# mainboard.net
KiCad netlist of a schematic drawn in EAGLE
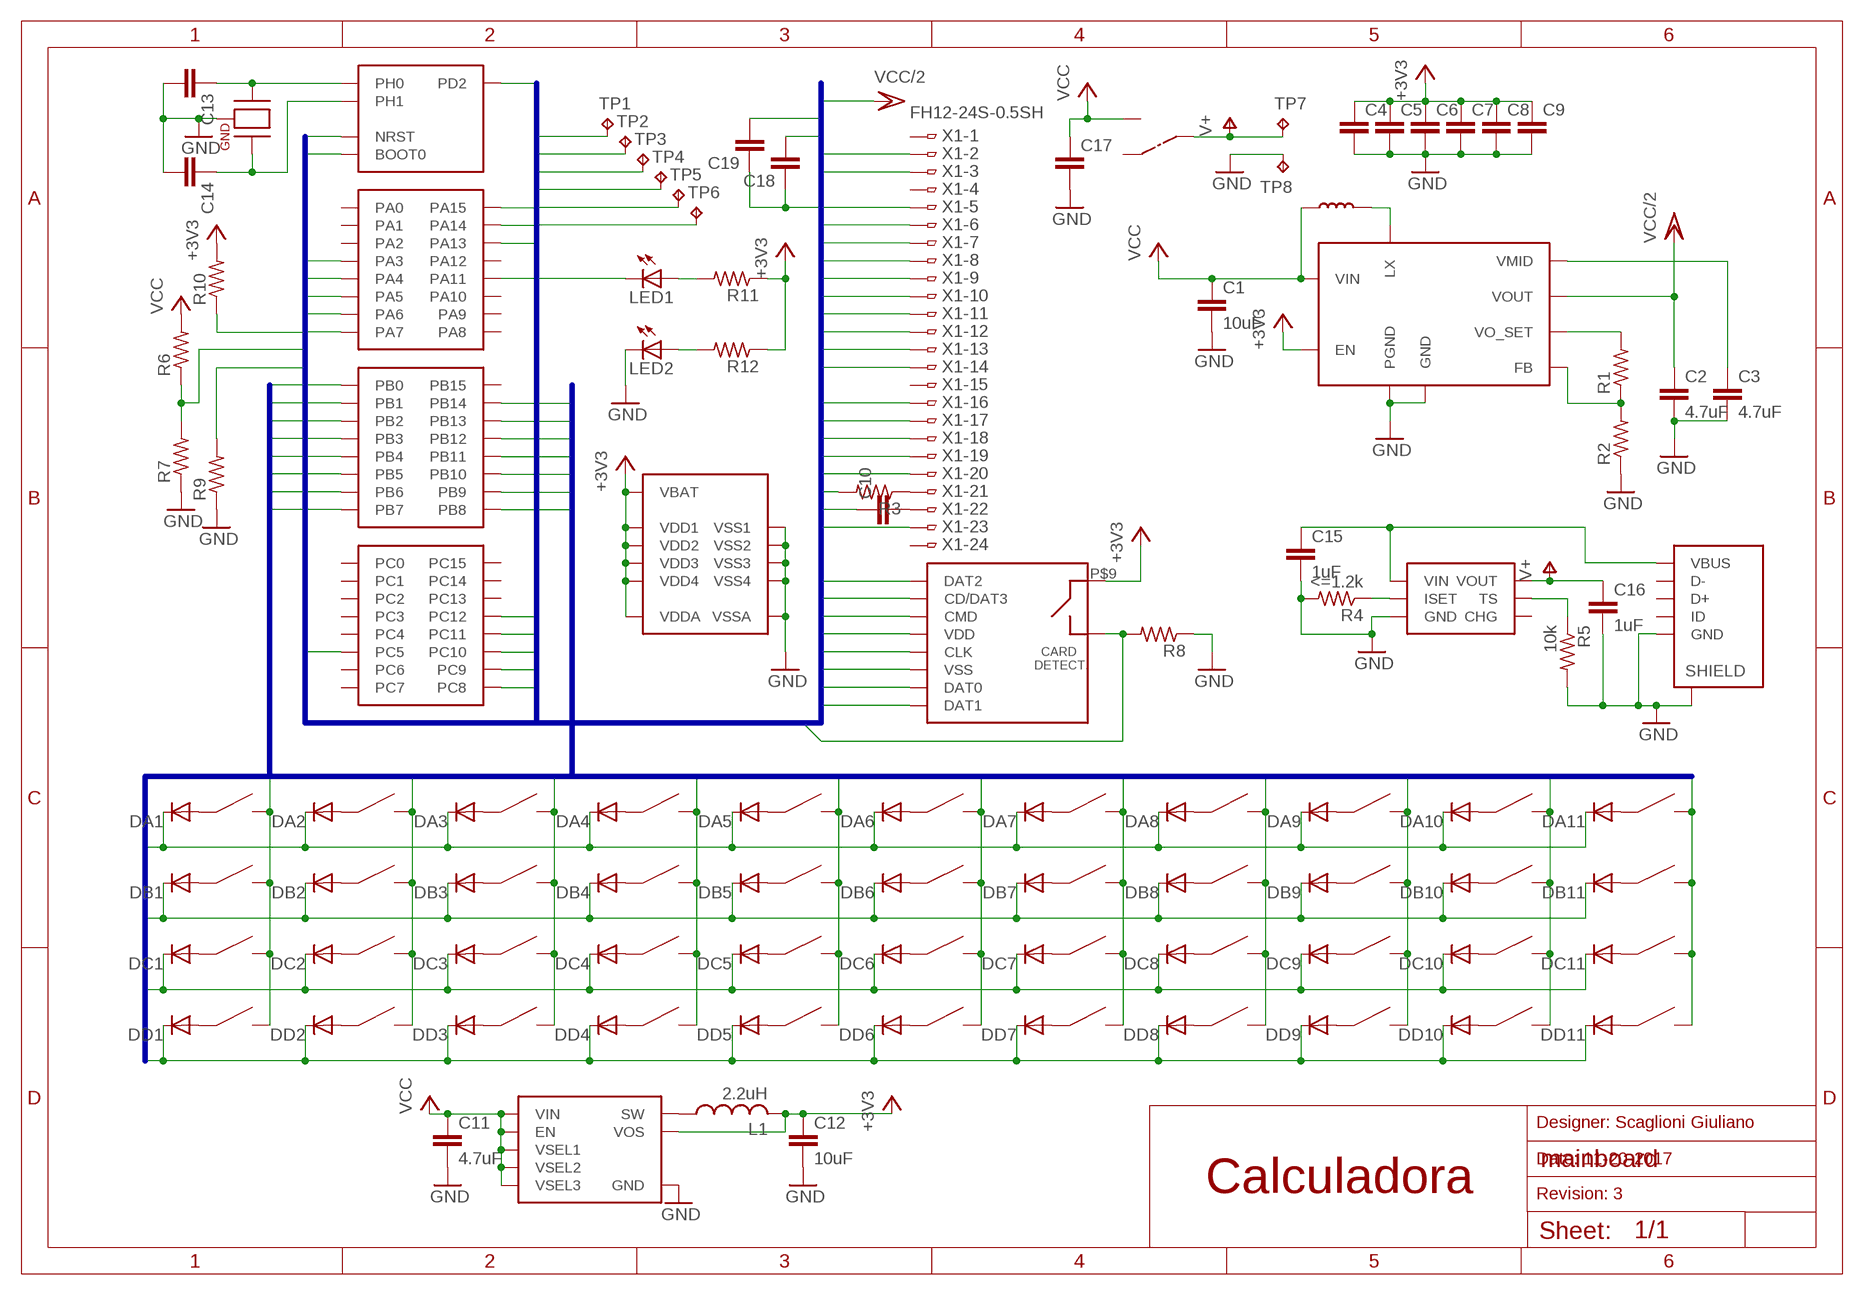
[diagram p0: schematic, sheet 1]

(export (version "E")
  (design (tool "Eeschema 10.0.6"))
  (components
    (comp (ref "BTA1")
      (value "WURTH_SWITCH")
      (footprint "eagle-import:WURTH_SWITCH_SMD")
      (libsource (lib "eagle-import") (part "WURTH_SWITCH"))
    )
    (comp (ref "BTA2")
      (value "WURTH_SWITCH")
      (footprint "eagle-import:WURTH_SWITCH_SMD")
      (libsource (lib "eagle-import") (part "WURTH_SWITCH"))
    )
    (comp (ref "BTA3")
      (value "WURTH_SWITCH")
      (footprint "eagle-import:WURTH_SWITCH_SMD")
      (libsource (lib "eagle-import") (part "WURTH_SWITCH"))
    )
    (comp (ref "BTA4")
      (value "WURTH_SWITCH")
      (footprint "eagle-import:WURTH_SWITCH_SMD")
      (libsource (lib "eagle-import") (part "WURTH_SWITCH"))
    )
    (comp (ref "BTA5")
      (value "WURTH_SWITCH")
      (footprint "eagle-import:WURTH_SWITCH_SMD")
      (libsource (lib "eagle-import") (part "WURTH_SWITCH"))
    )
    (comp (ref "BTA6")
      (value "WURTH_SWITCH")
      (footprint "eagle-import:WURTH_SWITCH_SMD")
      (libsource (lib "eagle-import") (part "WURTH_SWITCH"))
    )
    (comp (ref "BTA7")
      (value "WURTH_SWITCH")
      (footprint "eagle-import:WURTH_SWITCH_SMD")
      (libsource (lib "eagle-import") (part "WURTH_SWITCH"))
    )
    (comp (ref "BTA8")
      (value "WURTH_SWITCH")
      (footprint "eagle-import:WURTH_SWITCH_SMD")
      (libsource (lib "eagle-import") (part "WURTH_SWITCH"))
    )
    (comp (ref "BTA9")
      (value "WURTH_SWITCH")
      (footprint "eagle-import:WURTH_SWITCH_SMD")
      (libsource (lib "eagle-import") (part "WURTH_SWITCH"))
    )
    (comp (ref "BTA10")
      (value "WURTH_SWITCH")
      (footprint "eagle-import:WURTH_SWITCH_SMD")
      (libsource (lib "eagle-import") (part "WURTH_SWITCH"))
    )
    (comp (ref "BTA11")
      (value "WURTH_SWITCH")
      (footprint "eagle-import:WURTH_SWITCH_SMD")
      (libsource (lib "eagle-import") (part "WURTH_SWITCH"))
    )
    (comp (ref "BTB1")
      (value "WURTH_SWITCH")
      (footprint "eagle-import:WURTH_SWITCH_SMD")
      (libsource (lib "eagle-import") (part "WURTH_SWITCH"))
    )
    (comp (ref "BTB2")
      (value "WURTH_SWITCH")
      (footprint "eagle-import:WURTH_SWITCH_SMD")
      (libsource (lib "eagle-import") (part "WURTH_SWITCH"))
    )
    (comp (ref "BTB3")
      (value "WURTH_SWITCH")
      (footprint "eagle-import:WURTH_SWITCH_SMD")
      (libsource (lib "eagle-import") (part "WURTH_SWITCH"))
    )
    (comp (ref "BTB4")
      (value "WURTH_SWITCH")
      (footprint "eagle-import:WURTH_SWITCH_SMD")
      (libsource (lib "eagle-import") (part "WURTH_SWITCH"))
    )
    (comp (ref "BTB5")
      (value "WURTH_SWITCH")
      (footprint "eagle-import:WURTH_SWITCH_SMD")
      (libsource (lib "eagle-import") (part "WURTH_SWITCH"))
    )
    (comp (ref "BTB6")
      (value "WURTH_SWITCH")
      (footprint "eagle-import:WURTH_SWITCH_SMD")
      (libsource (lib "eagle-import") (part "WURTH_SWITCH"))
    )
    (comp (ref "BTB7")
      (value "WURTH_SWITCH")
      (footprint "eagle-import:WURTH_SWITCH_SMD")
      (libsource (lib "eagle-import") (part "WURTH_SWITCH"))
    )
    (comp (ref "BTB8")
      (value "WURTH_SWITCH")
      (footprint "eagle-import:WURTH_SWITCH_SMD")
      (libsource (lib "eagle-import") (part "WURTH_SWITCH"))
    )
    (comp (ref "BTB9")
      (value "WURTH_SWITCH")
      (footprint "eagle-import:WURTH_SWITCH_SMD")
      (libsource (lib "eagle-import") (part "WURTH_SWITCH"))
    )
    (comp (ref "BTB10")
      (value "WURTH_SWITCH")
      (footprint "eagle-import:WURTH_SWITCH_SMD")
      (libsource (lib "eagle-import") (part "WURTH_SWITCH"))
    )
    (comp (ref "BTB11")
      (value "WURTH_SWITCH")
      (footprint "eagle-import:WURTH_SWITCH_SMD")
      (libsource (lib "eagle-import") (part "WURTH_SWITCH"))
    )
    (comp (ref "BTC1")
      (value "WURTH_SWITCH")
      (footprint "eagle-import:WURTH_SWITCH_SMD")
      (libsource (lib "eagle-import") (part "WURTH_SWITCH"))
    )
    (comp (ref "BTC2")
      (value "WURTH_SWITCH")
      (footprint "eagle-import:WURTH_SWITCH_SMD")
      (libsource (lib "eagle-import") (part "WURTH_SWITCH"))
    )
    (comp (ref "BTC3")
      (value "WURTH_SWITCH")
      (footprint "eagle-import:WURTH_SWITCH_SMD")
      (libsource (lib "eagle-import") (part "WURTH_SWITCH"))
    )
    (comp (ref "BTC4")
      (value "WURTH_SWITCH")
      (footprint "eagle-import:WURTH_SWITCH_SMD")
      (libsource (lib "eagle-import") (part "WURTH_SWITCH"))
    )
    (comp (ref "BTC5")
      (value "WURTH_SWITCH")
      (footprint "eagle-import:WURTH_SWITCH_SMD")
      (libsource (lib "eagle-import") (part "WURTH_SWITCH"))
    )
    (comp (ref "BTC6")
      (value "WURTH_SWITCH")
      (footprint "eagle-import:WURTH_SWITCH_SMD")
      (libsource (lib "eagle-import") (part "WURTH_SWITCH"))
    )
    (comp (ref "BTC7")
      (value "WURTH_SWITCH")
      (footprint "eagle-import:WURTH_SWITCH_SMD")
      (libsource (lib "eagle-import") (part "WURTH_SWITCH"))
    )
    (comp (ref "BTC8")
      (value "WURTH_SWITCH")
      (footprint "eagle-import:WURTH_SWITCH_SMD")
      (libsource (lib "eagle-import") (part "WURTH_SWITCH"))
    )
    (comp (ref "BTC9")
      (value "WURTH_SWITCH")
      (footprint "eagle-import:WURTH_SWITCH_SMD")
      (libsource (lib "eagle-import") (part "WURTH_SWITCH"))
    )
    (comp (ref "BTC10")
      (value "WURTH_SWITCH")
      (footprint "eagle-import:WURTH_SWITCH_SMD")
      (libsource (lib "eagle-import") (part "WURTH_SWITCH"))
    )
    (comp (ref "BTC11")
      (value "WURTH_SWITCH")
      (footprint "eagle-import:WURTH_SWITCH_SMD")
      (libsource (lib "eagle-import") (part "WURTH_SWITCH"))
    )
    (comp (ref "BTD1")
      (value "WURTH_SWITCH")
      (footprint "eagle-import:WURTH_SWITCH_SMD")
      (libsource (lib "eagle-import") (part "WURTH_SWITCH"))
    )
    (comp (ref "BTD2")
      (value "WURTH_SWITCH")
      (footprint "eagle-import:WURTH_SWITCH_SMD")
      (libsource (lib "eagle-import") (part "WURTH_SWITCH"))
    )
    (comp (ref "BTD3")
      (value "WURTH_SWITCH")
      (footprint "eagle-import:WURTH_SWITCH_SMD")
      (libsource (lib "eagle-import") (part "WURTH_SWITCH"))
    )
    (comp (ref "BTD4")
      (value "WURTH_SWITCH")
      (footprint "eagle-import:WURTH_SWITCH_SMD")
      (libsource (lib "eagle-import") (part "WURTH_SWITCH"))
    )
    (comp (ref "BTD5")
      (value "WURTH_SWITCH")
      (footprint "eagle-import:WURTH_SWITCH_SMD")
      (libsource (lib "eagle-import") (part "WURTH_SWITCH"))
    )
    (comp (ref "BTD6")
      (value "WURTH_SWITCH")
      (footprint "eagle-import:WURTH_SWITCH_SMD")
      (libsource (lib "eagle-import") (part "WURTH_SWITCH"))
    )
    (comp (ref "BTD7")
      (value "WURTH_SWITCH")
      (footprint "eagle-import:WURTH_SWITCH_SMD")
      (libsource (lib "eagle-import") (part "WURTH_SWITCH"))
    )
    (comp (ref "BTD8")
      (value "WURTH_SWITCH")
      (footprint "eagle-import:WURTH_SWITCH_SMD")
      (libsource (lib "eagle-import") (part "WURTH_SWITCH"))
    )
    (comp (ref "BTD9")
      (value "WURTH_SWITCH")
      (footprint "eagle-import:WURTH_SWITCH_SMD")
      (libsource (lib "eagle-import") (part "WURTH_SWITCH"))
    )
    (comp (ref "BTD10")
      (value "WURTH_SWITCH")
      (footprint "eagle-import:WURTH_SWITCH_SMD")
      (libsource (lib "eagle-import") (part "WURTH_SWITCH"))
    )
    (comp (ref "BTD11")
      (value "WURTH_SWITCH")
      (footprint "eagle-import:WURTH_SWITCH_SMD")
      (libsource (lib "eagle-import") (part "WURTH_SWITCH"))
    )
    (comp (ref "C1")
      (value "10uF")
      (footprint "eagle-import:C0805")
      (libsource (lib "eagle-import") (part "resistor_348_C-EUC0805"))
    )
    (comp (ref "C2")
      (value "4.7uF")
      (footprint "eagle-import:C0805")
      (libsource (lib "eagle-import") (part "resistor_348_C-EUC0805"))
    )
    (comp (ref "C3")
      (value "4.7uF")
      (footprint "eagle-import:C0805")
      (libsource (lib "eagle-import") (part "resistor_348_C-EUC0805"))
    )
    (comp (ref "C4")
      (value "C-EUC0603")
      (footprint "eagle-import:C0603")
      (libsource (lib "eagle-import") (part "C-EUC0603"))
    )
    (comp (ref "C5")
      (value "C-EUC0603")
      (footprint "eagle-import:C0603")
      (libsource (lib "eagle-import") (part "C-EUC0603"))
    )
    (comp (ref "C6")
      (value "C-EUC0603")
      (footprint "eagle-import:C0603")
      (libsource (lib "eagle-import") (part "C-EUC0603"))
    )
    (comp (ref "C7")
      (value "C-EUC0603")
      (footprint "eagle-import:C0603")
      (libsource (lib "eagle-import") (part "C-EUC0603"))
    )
    (comp (ref "C8")
      (value "C-EUC0603")
      (footprint "eagle-import:C0603")
      (libsource (lib "eagle-import") (part "C-EUC0603"))
    )
    (comp (ref "C9")
      (value "C-EUC0603")
      (footprint "eagle-import:C0603")
      (libsource (lib "eagle-import") (part "C-EUC0603"))
    )
    (comp (ref "C10")
      (value "C-EUC0603")
      (footprint "eagle-import:C0603")
      (libsource (lib "eagle-import") (part "C-EUC0603"))
    )
    (comp (ref "C11")
      (value "4.7uF")
      (footprint "eagle-import:C0603")
      (libsource (lib "eagle-import") (part "C-EUC0603"))
    )
    (comp (ref "C12")
      (value "10uF")
      (footprint "eagle-import:C0603")
      (libsource (lib "eagle-import") (part "C-EUC0603"))
    )
    (comp (ref "C13")
      (value "CC0603")
      (footprint "eagle-import:C0603")
      (libsource (lib "eagle-import") (part "CC0603"))
    )
    (comp (ref "C14")
      (value "CC0603")
      (footprint "eagle-import:C0603")
      (libsource (lib "eagle-import") (part "CC0603"))
    )
    (comp (ref "C15")
      (value "1uF")
      (footprint "eagle-import:C0603")
      (libsource (lib "eagle-import") (part "C-EUC0603"))
    )
    (comp (ref "C16")
      (value "1uF")
      (footprint "eagle-import:C0603")
      (libsource (lib "eagle-import") (part "C-EUC0603"))
    )
    (comp (ref "C17")
      (value "CC1206")
      (footprint "eagle-import:C1206")
      (libsource (lib "eagle-import") (part "CC1206"))
    )
    (comp (ref "C18")
      (value "C-EUC0603")
      (footprint "eagle-import:C0603")
      (libsource (lib "eagle-import") (part "C-EUC0603"))
    )
    (comp (ref "C19")
      (value "C-EUC0603")
      (footprint "eagle-import:C0603")
      (libsource (lib "eagle-import") (part "C-EUC0603"))
    )
    (comp (ref "DA1")
      (value "DIODE-SOD523")
      (footprint "eagle-import:SOD523")
      (libsource (lib "eagle-import") (part "DIODE-SOD523"))
    )
    (comp (ref "DA2")
      (value "DIODE-SOD523")
      (footprint "eagle-import:SOD523")
      (libsource (lib "eagle-import") (part "DIODE-SOD523"))
    )
    (comp (ref "DA3")
      (value "DIODE-SOD523")
      (footprint "eagle-import:SOD523")
      (libsource (lib "eagle-import") (part "DIODE-SOD523"))
    )
    (comp (ref "DA4")
      (value "DIODE-SOD523")
      (footprint "eagle-import:SOD523")
      (libsource (lib "eagle-import") (part "DIODE-SOD523"))
    )
    (comp (ref "DA5")
      (value "DIODE-SOD523")
      (footprint "eagle-import:SOD523")
      (libsource (lib "eagle-import") (part "DIODE-SOD523"))
    )
    (comp (ref "DA6")
      (value "DIODE-SOD523")
      (footprint "eagle-import:SOD523")
      (libsource (lib "eagle-import") (part "DIODE-SOD523"))
    )
    (comp (ref "DA7")
      (value "DIODE-SOD523")
      (footprint "eagle-import:SOD523")
      (libsource (lib "eagle-import") (part "DIODE-SOD523"))
    )
    (comp (ref "DA8")
      (value "DIODE-SOD523")
      (footprint "eagle-import:SOD523")
      (libsource (lib "eagle-import") (part "DIODE-SOD523"))
    )
    (comp (ref "DA9")
      (value "DIODE-SOD523")
      (footprint "eagle-import:SOD523")
      (libsource (lib "eagle-import") (part "DIODE-SOD523"))
    )
    (comp (ref "DA10")
      (value "DIODE-SOD523")
      (footprint "eagle-import:SOD523")
      (libsource (lib "eagle-import") (part "DIODE-SOD523"))
    )
    (comp (ref "DA11")
      (value "DIODE-SOD523")
      (footprint "eagle-import:SOD523")
      (libsource (lib "eagle-import") (part "DIODE-SOD523"))
    )
    (comp (ref "DB1")
      (value "DIODE-SOD523")
      (footprint "eagle-import:SOD523")
      (libsource (lib "eagle-import") (part "DIODE-SOD523"))
    )
    (comp (ref "DB2")
      (value "DIODE-SOD523")
      (footprint "eagle-import:SOD523")
      (libsource (lib "eagle-import") (part "DIODE-SOD523"))
    )
    (comp (ref "DB3")
      (value "DIODE-SOD523")
      (footprint "eagle-import:SOD523")
      (libsource (lib "eagle-import") (part "DIODE-SOD523"))
    )
    (comp (ref "DB4")
      (value "DIODE-SOD523")
      (footprint "eagle-import:SOD523")
      (libsource (lib "eagle-import") (part "DIODE-SOD523"))
    )
    (comp (ref "DB5")
      (value "DIODE-SOD523")
      (footprint "eagle-import:SOD523")
      (libsource (lib "eagle-import") (part "DIODE-SOD523"))
    )
    (comp (ref "DB6")
      (value "DIODE-SOD523")
      (footprint "eagle-import:SOD523")
      (libsource (lib "eagle-import") (part "DIODE-SOD523"))
    )
    (comp (ref "DB7")
      (value "DIODE-SOD523")
      (footprint "eagle-import:SOD523")
      (libsource (lib "eagle-import") (part "DIODE-SOD523"))
    )
    (comp (ref "DB8")
      (value "DIODE-SOD523")
      (footprint "eagle-import:SOD523")
      (libsource (lib "eagle-import") (part "DIODE-SOD523"))
    )
    (comp (ref "DB9")
      (value "DIODE-SOD523")
      (footprint "eagle-import:SOD523")
      (libsource (lib "eagle-import") (part "DIODE-SOD523"))
    )
    (comp (ref "DB10")
      (value "DIODE-SOD523")
      (footprint "eagle-import:SOD523")
      (libsource (lib "eagle-import") (part "DIODE-SOD523"))
    )
    (comp (ref "DB11")
      (value "DIODE-SOD523")
      (footprint "eagle-import:SOD523")
      (libsource (lib "eagle-import") (part "DIODE-SOD523"))
    )
    (comp (ref "DC1")
      (value "DIODE-SOD523")
      (footprint "eagle-import:SOD523")
      (libsource (lib "eagle-import") (part "DIODE-SOD523"))
    )
    (comp (ref "DC2")
      (value "DIODE-SOD523")
      (footprint "eagle-import:SOD523")
      (libsource (lib "eagle-import") (part "DIODE-SOD523"))
    )
    (comp (ref "DC3")
      (value "DIODE-SOD523")
      (footprint "eagle-import:SOD523")
      (libsource (lib "eagle-import") (part "DIODE-SOD523"))
    )
    (comp (ref "DC4")
      (value "DIODE-SOD523")
      (footprint "eagle-import:SOD523")
      (libsource (lib "eagle-import") (part "DIODE-SOD523"))
    )
    (comp (ref "DC5")
      (value "DIODE-SOD523")
      (footprint "eagle-import:SOD523")
      (libsource (lib "eagle-import") (part "DIODE-SOD523"))
    )
    (comp (ref "DC6")
      (value "DIODE-SOD523")
      (footprint "eagle-import:SOD523")
      (libsource (lib "eagle-import") (part "DIODE-SOD523"))
    )
    (comp (ref "DC7")
      (value "DIODE-SOD523")
      (footprint "eagle-import:SOD523")
      (libsource (lib "eagle-import") (part "DIODE-SOD523"))
    )
    (comp (ref "DC8")
      (value "DIODE-SOD523")
      (footprint "eagle-import:SOD523")
      (libsource (lib "eagle-import") (part "DIODE-SOD523"))
    )
    (comp (ref "DC9")
      (value "DIODE-SOD523")
      (footprint "eagle-import:SOD523")
      (libsource (lib "eagle-import") (part "DIODE-SOD523"))
    )
    (comp (ref "DC10")
      (value "DIODE-SOD523")
      (footprint "eagle-import:SOD523")
      (libsource (lib "eagle-import") (part "DIODE-SOD523"))
    )
    (comp (ref "DC11")
      (value "DIODE-SOD523")
      (footprint "eagle-import:SOD523")
      (libsource (lib "eagle-import") (part "DIODE-SOD523"))
    )
    (comp (ref "DD1")
      (value "DIODE-SOD523")
      (footprint "eagle-import:SOD523")
      (libsource (lib "eagle-import") (part "DIODE-SOD523"))
    )
    (comp (ref "DD2")
      (value "DIODE-SOD523")
      (footprint "eagle-import:SOD523")
      (libsource (lib "eagle-import") (part "DIODE-SOD523"))
    )
    (comp (ref "DD3")
      (value "DIODE-SOD523")
      (footprint "eagle-import:SOD523")
      (libsource (lib "eagle-import") (part "DIODE-SOD523"))
    )
    (comp (ref "DD4")
      (value "DIODE-SOD523")
      (footprint "eagle-import:SOD523")
      (libsource (lib "eagle-import") (part "DIODE-SOD523"))
    )
    (comp (ref "DD5")
      (value "DIODE-SOD523")
      (footprint "eagle-import:SOD523")
      (libsource (lib "eagle-import") (part "DIODE-SOD523"))
    )
    (comp (ref "DD6")
      (value "DIODE-SOD523")
      (footprint "eagle-import:SOD523")
      (libsource (lib "eagle-import") (part "DIODE-SOD523"))
    )
    (comp (ref "DD7")
      (value "DIODE-SOD523")
      (footprint "eagle-import:SOD523")
      (libsource (lib "eagle-import") (part "DIODE-SOD523"))
    )
    (comp (ref "DD8")
      (value "DIODE-SOD523")
      (footprint "eagle-import:SOD523")
      (libsource (lib "eagle-import") (part "DIODE-SOD523"))
    )
    (comp (ref "DD9")
      (value "DIODE-SOD523")
      (footprint "eagle-import:SOD523")
      (libsource (lib "eagle-import") (part "DIODE-SOD523"))
    )
    (comp (ref "DD10")
      (value "DIODE-SOD523")
      (footprint "eagle-import:SOD523")
      (libsource (lib "eagle-import") (part "DIODE-SOD523"))
    )
    (comp (ref "DD11")
      (value "DIODE-SOD523")
      (footprint "eagle-import:SOD523")
      (libsource (lib "eagle-import") (part "DIODE-SOD523"))
    )
    (comp (ref "L1")
      (value "2.2uH")
      (footprint "eagle-import:L2012C")
      (libsource (lib "eagle-import") (part "L-USL2012C"))
    )
    (comp (ref "LED1")
      (value "LED_ESML0603")
      (footprint "eagle-import:LED_SML0603")
      (libsource (lib "eagle-import") (part "LED_ESML0603"))
    )
    (comp (ref "LED2")
      (value "LED_ESML0603")
      (footprint "eagle-import:LED_SML0603")
      (libsource (lib "eagle-import") (part "LED_ESML0603"))
    )
    (comp (ref "R1")
      (value "R-US_R0402")
      (footprint "eagle-import:R0402")
      (libsource (lib "eagle-import") (part "R-US_R0402"))
    )
    (comp (ref "R2")
      (value "R-US_R0402")
      (footprint "eagle-import:R0402")
      (libsource (lib "eagle-import") (part "R-US_R0402"))
    )
    (comp (ref "R3")
      (value "R-US_R0402")
      (footprint "eagle-import:R0402")
      (libsource (lib "eagle-import") (part "R-US_R0402"))
    )
    (comp (ref "R4")
      (value "<=1.2k")
      (footprint "eagle-import:R0402")
      (libsource (lib "eagle-import") (part "R-US_R0402"))
    )
    (comp (ref "R5")
      (value "10k")
      (footprint "eagle-import:R0402")
      (libsource (lib "eagle-import") (part "R-US_R0402"))
    )
    (comp (ref "R6")
      (value "R-US_R0402")
      (footprint "eagle-import:R0402")
      (libsource (lib "eagle-import") (part "R-US_R0402"))
    )
    (comp (ref "R7")
      (value "R-US_R0402")
      (footprint "eagle-import:R0402")
      (libsource (lib "eagle-import") (part "R-US_R0402"))
    )
    (comp (ref "R8")
      (value "R-US_R0402")
      (footprint "eagle-import:R0402")
      (libsource (lib "eagle-import") (part "R-US_R0402"))
    )
    (comp (ref "R9")
      (value "R-US_R0402")
      (footprint "eagle-import:R0402")
      (libsource (lib "eagle-import") (part "R-US_R0402"))
    )
    (comp (ref "R10")
      (value "R-US_R0402")
      (footprint "eagle-import:R0402")
      (libsource (lib "eagle-import") (part "R-US_R0402"))
    )
    (comp (ref "R11")
      (value "R-US_R0402")
      (footprint "eagle-import:R0402")
      (libsource (lib "eagle-import") (part "R-US_R0402"))
    )
    (comp (ref "R12")
      (value "R-US_R0402")
      (footprint "eagle-import:R0402")
      (libsource (lib "eagle-import") (part "R-US_R0402"))
    )
    (comp (ref "TP1")
      (value "TPTP20SQ")
      (footprint "eagle-import:TP20SQ")
      (libsource (lib "eagle-import") (part "TPTP20SQ"))
    )
    (comp (ref "TP2")
      (value "TPTP20SQ")
      (footprint "eagle-import:TP20SQ")
      (libsource (lib "eagle-import") (part "TPTP20SQ"))
    )
    (comp (ref "TP3")
      (value "TPTP20SQ")
      (footprint "eagle-import:TP20SQ")
      (libsource (lib "eagle-import") (part "TPTP20SQ"))
    )
    (comp (ref "TP4")
      (value "TPTP20SQ")
      (footprint "eagle-import:TP20SQ")
      (libsource (lib "eagle-import") (part "TPTP20SQ"))
    )
    (comp (ref "TP5")
      (value "TPTP20SQ")
      (footprint "eagle-import:TP20SQ")
      (libsource (lib "eagle-import") (part "TPTP20SQ"))
    )
    (comp (ref "TP6")
      (value "TPTP20SQ")
      (footprint "eagle-import:TP20SQ")
      (libsource (lib "eagle-import") (part "TPTP20SQ"))
    )
    (comp (ref "TP7")
      (value "TPTP20SQ")
      (footprint "eagle-import:TP20SQ")
      (libsource (lib "eagle-import") (part "TPTP20SQ"))
    )
    (comp (ref "TP8")
      (value "TPTP20SQ")
      (footprint "eagle-import:TP20SQ")
      (libsource (lib "eagle-import") (part "TPTP20SQ"))
    )
    (comp (ref "U$1")
      (value "STM32L471RGT6")
      (footprint "eagle-import:LQFP64")
      (libsource (lib "eagle-import") (part "STM32L471RGT6"))
    )
    (comp (ref "U$2")
      (value "DM3AT-SF-PEJM5")
      (footprint "eagle-import:DM3AT-SF-PEJM5_MICROSDREADER")
      (libsource (lib "eagle-import") (part "DM3AT-SF-PEJM5"))
    )
    (comp (ref "U$3")
      (value "MOLEX_47346-1001")
      (footprint "eagle-import:MOLEX_47346-1001")
      (libsource (lib "eagle-import") (part "MOLEX_47346-1001"))
    )
    (comp (ref "U$4")
      (value "STOD1317BTPUR")
      (footprint "eagle-import:DFN12L")
      (libsource (lib "eagle-import") (part "STOD1317BTPUR"))
    )
    (comp (ref "U$5")
      (value "VLS252010HBU")
      (footprint "eagle-import:VLS252010HBU")
      (libsource (lib "eagle-import") (part "VLS252010HBU"))
    )
    (comp (ref "U$6")
      (value "TPS627431YFPR")
      (footprint "eagle-import:BGA8")
      (libsource (lib "eagle-import") (part "TPS627431YFPR"))
    )
    (comp (ref "U$7")
      (value "CX5032SA")
      (footprint "eagle-import:CRYSTAL_5X3.2")
      (libsource (lib "eagle-import") (part "CX5032SA"))
    )
    (comp (ref "U$8")
      (value "BQ21040DBVR")
      (footprint "eagle-import:6-SOT-23")
      (libsource (lib "eagle-import") (part "BQ21040DBVR"))
    )
    (comp (ref "U$9")
      (value "ALPS_SSSS810701")
      (footprint "eagle-import:ALPS_SSSS810701")
      (libsource (lib "eagle-import") (part "ALPS_SSSS810701"))
    )
    (comp (ref "X1")
      (value "FH12-24S-0.5SH")
      (footprint "eagle-import:FH12-24S-0.5SH")
      (fields (field (name "MPN") "FH12-24S-0.5SH(55)"))
      (libsource (lib "eagle-import") (part "FH12-24S-0.5SH"))
    )
  )
  (nets
    (net (code "1") (name "+3V3") (class "Default")
      (node (ref "C12") (pin "1") (pinfunction "1_1") (pintype "passive"))
      (node (ref "C18") (pin "2") (pinfunction "2_2") (pintype "passive"))
      (node (ref "C4") (pin "1") (pinfunction "1_1") (pintype "passive"))
      (node (ref "C5") (pin "1") (pinfunction "1_1") (pintype "passive"))
      (node (ref "C6") (pin "1") (pinfunction "1_1") (pintype "passive"))
      (node (ref "C7") (pin "1") (pinfunction "1_1") (pintype "passive"))
      (node (ref "C8") (pin "1") (pinfunction "1_1") (pintype "passive"))
      (node (ref "C9") (pin "1") (pinfunction "1_1") (pintype "passive"))
      (node (ref "L1") (pin "2") (pinfunction "2_2") (pintype "passive"))
      (node (ref "R10") (pin "2") (pinfunction "2_2") (pintype "passive"))
      (node (ref "R11") (pin "1") (pinfunction "1_1") (pintype "passive"))
      (node (ref "R12") (pin "1") (pinfunction "1_1") (pintype "passive"))
      (node (ref "TP1") (pin "TP") (pinfunction "TP_TP") (pintype "input"))
      (node (ref "U$1") (pin "P$1") (pinfunction "VBAT_P$1") (pintype "bidirectional"))
      (node (ref "U$1") (pin "P$13") (pinfunction "VDDA_P$13") (pintype "bidirectional"))
      (node (ref "U$1") (pin "P$19") (pinfunction "VDD1_P$19") (pintype "bidirectional"))
      (node (ref "U$1") (pin "P$32") (pinfunction "VDD2_P$32") (pintype "bidirectional"))
      (node (ref "U$1") (pin "P$48") (pinfunction "VDD3_P$48") (pintype "bidirectional"))
      (node (ref "U$1") (pin "P$64") (pinfunction "VDD4_P$64") (pintype "bidirectional"))
      (node (ref "U$2") (pin "P$4") (pinfunction "VDD_P$4") (pintype "bidirectional"))
      (node (ref "U$2") (pin "P$9") (pinfunction "P$9_P$9") (pintype "bidirectional"))
      (node (ref "U$4") (pin "P6") (pinfunction "EN_P6") (pintype "bidirectional"))
      (node (ref "U$6") (pin "C2") (pinfunction "VOS_C2") (pintype "bidirectional"))
      (node (ref "X1") (pin "5") (pinfunction "1_5") (pintype "passive"))
      (node (ref "X1") (pin "9") (pinfunction "1_9") (pintype "passive"))
    )
    (net (code "3") (name "BAT_SENS") (class "Default")
      (node (ref "R6") (pin "1") (pinfunction "1_1") (pintype "passive"))
      (node (ref "R7") (pin "2") (pinfunction "2_2") (pintype "passive"))
      (node (ref "U$1") (pin "P$25") (pinfunction "PC5_P$25") (pintype "bidirectional"))
    )
    (net (code "4") (name "BOOT0") (class "Default")
      (node (ref "R9") (pin "2") (pinfunction "2_2") (pintype "passive"))
      (node (ref "TP5") (pin "TP") (pinfunction "TP_TP") (pintype "input"))
      (node (ref "U$1") (pin "P$60") (pinfunction "BOOT0_P$60") (pintype "bidirectional"))
    )
    (net (code "5") (name "GND") (class "Default")
      (node (ref "C1") (pin "2") (pinfunction "2_2") (pintype "passive"))
      (node (ref "C10") (pin "1") (pinfunction "1_1") (pintype "passive"))
      (node (ref "C11") (pin "2") (pinfunction "2_2") (pintype "passive"))
      (node (ref "C12") (pin "2") (pinfunction "2_2") (pintype "passive"))
      (node (ref "C13") (pin "2") (pinfunction "2_2") (pintype "passive"))
      (node (ref "C14") (pin "2") (pinfunction "2_2") (pintype "passive"))
      (node (ref "C15") (pin "2") (pinfunction "2_2") (pintype "passive"))
      (node (ref "C16") (pin "2") (pinfunction "2_2") (pintype "passive"))
      (node (ref "C17") (pin "2") (pinfunction "2_2") (pintype "passive"))
      (node (ref "C18") (pin "1") (pinfunction "1_1") (pintype "passive"))
      (node (ref "C19") (pin "1") (pinfunction "1_1") (pintype "passive"))
      (node (ref "C2") (pin "2") (pinfunction "2_2") (pintype "passive"))
      (node (ref "C3") (pin "2") (pinfunction "2_2") (pintype "passive"))
      (node (ref "C4") (pin "2") (pinfunction "2_2") (pintype "passive"))
      (node (ref "C5") (pin "2") (pinfunction "2_2") (pintype "passive"))
      (node (ref "C6") (pin "2") (pinfunction "2_2") (pintype "passive"))
      (node (ref "C7") (pin "2") (pinfunction "2_2") (pintype "passive"))
      (node (ref "C8") (pin "2") (pinfunction "2_2") (pintype "passive"))
      (node (ref "C9") (pin "2") (pinfunction "2_2") (pintype "passive"))
      (node (ref "LED2") (pin "C") (pinfunction "C_C") (pintype "passive"))
      (node (ref "R2") (pin "1") (pinfunction "1_1") (pintype "passive"))
      (node (ref "R3") (pin "2") (pinfunction "2_2") (pintype "passive"))
      (node (ref "R4") (pin "2") (pinfunction "2_2") (pintype "passive"))
      (node (ref "R5") (pin "2") (pinfunction "2_2") (pintype "passive"))
      (node (ref "R7") (pin "1") (pinfunction "1_1") (pintype "passive"))
      (node (ref "R8") (pin "1") (pinfunction "1_1") (pintype "passive"))
      (node (ref "R9") (pin "1") (pinfunction "1_1") (pintype "passive"))
      (node (ref "TP4") (pin "TP") (pinfunction "TP_TP") (pintype "input"))
      (node (ref "TP8") (pin "TP") (pinfunction "TP_TP") (pintype "input"))
      (node (ref "U$1") (pin "P$12") (pinfunction "VSSA_P$12") (pintype "bidirectional"))
      (node (ref "U$1") (pin "P$18") (pinfunction "VSS1_P$18") (pintype "bidirectional"))
      (node (ref "U$1") (pin "P$31") (pinfunction "VSS2_P$31") (pintype "bidirectional"))
      (node (ref "U$1") (pin "P$47") (pinfunction "VSS3_P$47") (pintype "bidirectional"))
      (node (ref "U$1") (pin "P$63") (pinfunction "VSS4_P$63") (pintype "bidirectional"))
      (node (ref "U$2") (pin "P$6") (pinfunction "VSS_P$6") (pintype "bidirectional"))
      (node (ref "U$3") (pin "MECH1") (pinfunction "P$6_MECH1") (pintype "bidirectional"))
      (node (ref "U$3") (pin "MECH2") (pinfunction "P$6_MECH2") (pintype "bidirectional"))
      (node (ref "U$3") (pin "MECH3") (pinfunction "P$6_MECH3") (pintype "bidirectional"))
      (node (ref "U$3") (pin "MECH4") (pinfunction "P$6_MECH4") (pintype "bidirectional"))
      (node (ref "U$3") (pin "MECH5") (pinfunction "P$6_MECH5") (pintype "bidirectional"))
      (node (ref "U$3") (pin "MECH6") (pinfunction "P$6_MECH6") (pintype "bidirectional"))
      (node (ref "U$3") (pin "P$5") (pinfunction "GND_P$5") (pintype "bidirectional"))
      (node (ref "U$4") (pin "P10") (pinfunction "PGND_P10") (pintype "bidirectional"))
      (node (ref "U$4") (pin "P4") (pinfunction "GND_P4") (pintype "bidirectional"))
      (node (ref "U$4") (pin "P9") (pinfunction "PGND_P9") (pintype "bidirectional"))
      (node (ref "U$6") (pin "B2") (pinfunction "GND_B2") (pintype "bidirectional"))
      (node (ref "U$7") (pin "P$2") (pinfunction "GND_P$2") (pintype "bidirectional"))
      (node (ref "U$7") (pin "P$4") (pinfunction "GND_P$4") (pintype "bidirectional"))
      (node (ref "U$8") (pin "P$5") (pinfunction "GND_P$5") (pintype "bidirectional"))
      (node (ref "X1") (pin "11") (pinfunction "1_11") (pintype "passive"))
      (node (ref "X1") (pin "12") (pinfunction "1_12") (pintype "passive"))
      (node (ref "X1") (pin "16") (pinfunction "1_16") (pintype "passive"))
      (node (ref "X1") (pin "17") (pinfunction "1_17") (pintype "passive"))
      (node (ref "X1") (pin "18") (pinfunction "1_18") (pintype "passive"))
      (node (ref "X1") (pin "19") (pinfunction "1_19") (pintype "passive"))
      (node (ref "X1") (pin "2") (pinfunction "1_2") (pintype "passive"))
      (node (ref "X1") (pin "20") (pinfunction "1_20") (pintype "passive"))
      (node (ref "X1") (pin "3") (pinfunction "1_3") (pintype "passive"))
      (node (ref "X1") (pin "6") (pinfunction "1_6") (pintype "passive"))
      (node (ref "X1") (pin "7") (pinfunction "1_7") (pintype "passive"))
    )
    (net (code "6") (name "KEYCOL0") (class "Default")
      (node (ref "BTA1") (pin "P$2") (pinfunction "P$2_P$2") (pintype "bidirectional"))
      (node (ref "BTA1") (pin "P$4") (pinfunction "P$2_P$4") (pintype "bidirectional"))
      (node (ref "BTB1") (pin "P$2") (pinfunction "P$2_P$2") (pintype "bidirectional"))
      (node (ref "BTB1") (pin "P$4") (pinfunction "P$2_P$4") (pintype "bidirectional"))
      (node (ref "BTC1") (pin "P$2") (pinfunction "P$2_P$2") (pintype "bidirectional"))
      (node (ref "BTC1") (pin "P$4") (pinfunction "P$2_P$4") (pintype "bidirectional"))
      (node (ref "BTD1") (pin "P$2") (pinfunction "P$2_P$2") (pintype "bidirectional"))
      (node (ref "BTD1") (pin "P$4") (pinfunction "P$2_P$4") (pintype "bidirectional"))
      (node (ref "U$1") (pin "P$26") (pinfunction "PB0_P$26") (pintype "bidirectional"))
    )
    (net (code "7") (name "KEYCOL1") (class "Default")
      (node (ref "BTA2") (pin "P$2") (pinfunction "P$2_P$2") (pintype "bidirectional"))
      (node (ref "BTA2") (pin "P$4") (pinfunction "P$2_P$4") (pintype "bidirectional"))
      (node (ref "BTB2") (pin "P$2") (pinfunction "P$2_P$2") (pintype "bidirectional"))
      (node (ref "BTB2") (pin "P$4") (pinfunction "P$2_P$4") (pintype "bidirectional"))
      (node (ref "BTC2") (pin "P$2") (pinfunction "P$2_P$2") (pintype "bidirectional"))
      (node (ref "BTC2") (pin "P$4") (pinfunction "P$2_P$4") (pintype "bidirectional"))
      (node (ref "BTD2") (pin "P$2") (pinfunction "P$2_P$2") (pintype "bidirectional"))
      (node (ref "BTD2") (pin "P$4") (pinfunction "P$2_P$4") (pintype "bidirectional"))
      (node (ref "U$1") (pin "P$27") (pinfunction "PB1_P$27") (pintype "bidirectional"))
    )
    (net (code "8") (name "KEYCOL2") (class "Default")
      (node (ref "BTA3") (pin "P$2") (pinfunction "P$2_P$2") (pintype "bidirectional"))
      (node (ref "BTA3") (pin "P$4") (pinfunction "P$2_P$4") (pintype "bidirectional"))
      (node (ref "BTB3") (pin "P$2") (pinfunction "P$2_P$2") (pintype "bidirectional"))
      (node (ref "BTB3") (pin "P$4") (pinfunction "P$2_P$4") (pintype "bidirectional"))
      (node (ref "BTC3") (pin "P$2") (pinfunction "P$2_P$2") (pintype "bidirectional"))
      (node (ref "BTC3") (pin "P$4") (pinfunction "P$2_P$4") (pintype "bidirectional"))
      (node (ref "BTD3") (pin "P$2") (pinfunction "P$2_P$2") (pintype "bidirectional"))
      (node (ref "BTD3") (pin "P$4") (pinfunction "P$2_P$4") (pintype "bidirectional"))
      (node (ref "U$1") (pin "P$28") (pinfunction "PB2_P$28") (pintype "bidirectional"))
    )
    (net (code "9") (name "KEYCOL3") (class "Default")
      (node (ref "BTA4") (pin "P$2") (pinfunction "P$2_P$2") (pintype "bidirectional"))
      (node (ref "BTA4") (pin "P$4") (pinfunction "P$2_P$4") (pintype "bidirectional"))
      (node (ref "BTB4") (pin "P$2") (pinfunction "P$2_P$2") (pintype "bidirectional"))
      (node (ref "BTB4") (pin "P$4") (pinfunction "P$2_P$4") (pintype "bidirectional"))
      (node (ref "BTC4") (pin "P$2") (pinfunction "P$2_P$2") (pintype "bidirectional"))
      (node (ref "BTC4") (pin "P$4") (pinfunction "P$2_P$4") (pintype "bidirectional"))
      (node (ref "BTD4") (pin "P$2") (pinfunction "P$2_P$2") (pintype "bidirectional"))
      (node (ref "BTD4") (pin "P$4") (pinfunction "P$2_P$4") (pintype "bidirectional"))
      (node (ref "U$1") (pin "P$55") (pinfunction "PB3_P$55") (pintype "bidirectional"))
    )
    (net (code "10") (name "KEYCOL4") (class "Default")
      (node (ref "BTA5") (pin "P$2") (pinfunction "P$2_P$2") (pintype "bidirectional"))
      (node (ref "BTA5") (pin "P$4") (pinfunction "P$2_P$4") (pintype "bidirectional"))
      (node (ref "BTB5") (pin "P$2") (pinfunction "P$2_P$2") (pintype "bidirectional"))
      (node (ref "BTB5") (pin "P$4") (pinfunction "P$2_P$4") (pintype "bidirectional"))
      (node (ref "BTC5") (pin "P$2") (pinfunction "P$2_P$2") (pintype "bidirectional"))
      (node (ref "BTC5") (pin "P$4") (pinfunction "P$2_P$4") (pintype "bidirectional"))
      (node (ref "BTD5") (pin "P$2") (pinfunction "P$2_P$2") (pintype "bidirectional"))
      (node (ref "BTD5") (pin "P$4") (pinfunction "P$2_P$4") (pintype "bidirectional"))
      (node (ref "U$1") (pin "P$56") (pinfunction "PB4_P$56") (pintype "bidirectional"))
    )
    (net (code "11") (name "KEYCOL5") (class "Default")
      (node (ref "BTA6") (pin "P$2") (pinfunction "P$2_P$2") (pintype "bidirectional"))
      (node (ref "BTA6") (pin "P$4") (pinfunction "P$2_P$4") (pintype "bidirectional"))
      (node (ref "BTB6") (pin "P$2") (pinfunction "P$2_P$2") (pintype "bidirectional"))
      (node (ref "BTB6") (pin "P$4") (pinfunction "P$2_P$4") (pintype "bidirectional"))
      (node (ref "BTC6") (pin "P$2") (pinfunction "P$2_P$2") (pintype "bidirectional"))
      (node (ref "BTC6") (pin "P$4") (pinfunction "P$2_P$4") (pintype "bidirectional"))
      (node (ref "BTD6") (pin "P$2") (pinfunction "P$2_P$2") (pintype "bidirectional"))
      (node (ref "BTD6") (pin "P$4") (pinfunction "P$2_P$4") (pintype "bidirectional"))
      (node (ref "U$1") (pin "P$57") (pinfunction "PB5_P$57") (pintype "bidirectional"))
    )
    (net (code "12") (name "KEYCOL6") (class "Default")
      (node (ref "BTA7") (pin "P$2") (pinfunction "P$2_P$2") (pintype "bidirectional"))
      (node (ref "BTA7") (pin "P$4") (pinfunction "P$2_P$4") (pintype "bidirectional"))
      (node (ref "BTB7") (pin "P$2") (pinfunction "P$2_P$2") (pintype "bidirectional"))
      (node (ref "BTB7") (pin "P$4") (pinfunction "P$2_P$4") (pintype "bidirectional"))
      (node (ref "BTC7") (pin "P$2") (pinfunction "P$2_P$2") (pintype "bidirectional"))
      (node (ref "BTC7") (pin "P$4") (pinfunction "P$2_P$4") (pintype "bidirectional"))
      (node (ref "BTD7") (pin "P$2") (pinfunction "P$2_P$2") (pintype "bidirectional"))
      (node (ref "BTD7") (pin "P$4") (pinfunction "P$2_P$4") (pintype "bidirectional"))
      (node (ref "U$1") (pin "P$58") (pinfunction "PB6_P$58") (pintype "bidirectional"))
    )
    (net (code "13") (name "KEYCOL7") (class "Default")
      (node (ref "BTA8") (pin "P$2") (pinfunction "P$2_P$2") (pintype "bidirectional"))
      (node (ref "BTA8") (pin "P$4") (pinfunction "P$2_P$4") (pintype "bidirectional"))
      (node (ref "BTB8") (pin "P$2") (pinfunction "P$2_P$2") (pintype "bidirectional"))
      (node (ref "BTB8") (pin "P$4") (pinfunction "P$2_P$4") (pintype "bidirectional"))
      (node (ref "BTC8") (pin "P$2") (pinfunction "P$2_P$2") (pintype "bidirectional"))
      (node (ref "BTC8") (pin "P$4") (pinfunction "P$2_P$4") (pintype "bidirectional"))
      (node (ref "BTD8") (pin "P$2") (pinfunction "P$2_P$2") (pintype "bidirectional"))
      (node (ref "BTD8") (pin "P$4") (pinfunction "P$2_P$4") (pintype "bidirectional"))
      (node (ref "U$1") (pin "P$59") (pinfunction "PB7_P$59") (pintype "bidirectional"))
    )
    (net (code "14") (name "KEYCOL8") (class "Default")
      (node (ref "BTA9") (pin "P$2") (pinfunction "P$2_P$2") (pintype "bidirectional"))
      (node (ref "BTA9") (pin "P$4") (pinfunction "P$2_P$4") (pintype "bidirectional"))
      (node (ref "BTB9") (pin "P$2") (pinfunction "P$2_P$2") (pintype "bidirectional"))
      (node (ref "BTB9") (pin "P$4") (pinfunction "P$2_P$4") (pintype "bidirectional"))
      (node (ref "BTC9") (pin "P$2") (pinfunction "P$2_P$2") (pintype "bidirectional"))
      (node (ref "BTC9") (pin "P$4") (pinfunction "P$2_P$4") (pintype "bidirectional"))
      (node (ref "BTD9") (pin "P$2") (pinfunction "P$2_P$2") (pintype "bidirectional"))
      (node (ref "BTD9") (pin "P$4") (pinfunction "P$2_P$4") (pintype "bidirectional"))
      (node (ref "U$1") (pin "P$61") (pinfunction "PB8_P$61") (pintype "bidirectional"))
    )
    (net (code "15") (name "KEYCOL9") (class "Default")
      (node (ref "BTA10") (pin "P$2") (pinfunction "P$2_P$2") (pintype "bidirectional"))
      (node (ref "BTA10") (pin "P$4") (pinfunction "P$2_P$4") (pintype "bidirectional"))
      (node (ref "BTB10") (pin "P$2") (pinfunction "P$2_P$2") (pintype "bidirectional"))
      (node (ref "BTB10") (pin "P$4") (pinfunction "P$2_P$4") (pintype "bidirectional"))
      (node (ref "BTC10") (pin "P$2") (pinfunction "P$2_P$2") (pintype "bidirectional"))
      (node (ref "BTC10") (pin "P$4") (pinfunction "P$2_P$4") (pintype "bidirectional"))
      (node (ref "BTD10") (pin "P$2") (pinfunction "P$2_P$2") (pintype "bidirectional"))
      (node (ref "BTD10") (pin "P$4") (pinfunction "P$2_P$4") (pintype "bidirectional"))
      (node (ref "U$1") (pin "P$62") (pinfunction "PB9_P$62") (pintype "bidirectional"))
    )
    (net (code "16") (name "KEYCOL10") (class "Default")
      (node (ref "BTA11") (pin "P$2") (pinfunction "P$2_P$2") (pintype "bidirectional"))
      (node (ref "BTA11") (pin "P$4") (pinfunction "P$2_P$4") (pintype "bidirectional"))
      (node (ref "BTB11") (pin "P$2") (pinfunction "P$2_P$2") (pintype "bidirectional"))
      (node (ref "BTB11") (pin "P$4") (pinfunction "P$2_P$4") (pintype "bidirectional"))
      (node (ref "BTC11") (pin "P$2") (pinfunction "P$2_P$2") (pintype "bidirectional"))
      (node (ref "BTC11") (pin "P$4") (pinfunction "P$2_P$4") (pintype "bidirectional"))
      (node (ref "BTD11") (pin "P$2") (pinfunction "P$2_P$2") (pintype "bidirectional"))
      (node (ref "BTD11") (pin "P$4") (pinfunction "P$2_P$4") (pintype "bidirectional"))
      (node (ref "U$1") (pin "P$29") (pinfunction "PB10_P$29") (pintype "bidirectional"))
    )
    (net (code "17") (name "KEYROW1") (class "Default")
      (node (ref "DB1") (pin "C") (pinfunction "C_C") (pintype "passive"))
      (node (ref "DB10") (pin "C") (pinfunction "C_C") (pintype "passive"))
      (node (ref "DB11") (pin "C") (pinfunction "C_C") (pintype "passive"))
      (node (ref "DB2") (pin "C") (pinfunction "C_C") (pintype "passive"))
      (node (ref "DB3") (pin "C") (pinfunction "C_C") (pintype "passive"))
      (node (ref "DB4") (pin "C") (pinfunction "C_C") (pintype "passive"))
      (node (ref "DB5") (pin "C") (pinfunction "C_C") (pintype "passive"))
      (node (ref "DB6") (pin "C") (pinfunction "C_C") (pintype "passive"))
      (node (ref "DB7") (pin "C") (pinfunction "C_C") (pintype "passive"))
      (node (ref "DB8") (pin "C") (pinfunction "C_C") (pintype "passive"))
      (node (ref "DB9") (pin "C") (pinfunction "C_C") (pintype "passive"))
      (node (ref "U$1") (pin "P$34") (pinfunction "PB13_P$34") (pintype "bidirectional"))
    )
    (net (code "18") (name "KEYROW2") (class "Default")
      (node (ref "DC1") (pin "C") (pinfunction "C_C") (pintype "passive"))
      (node (ref "DC10") (pin "C") (pinfunction "C_C") (pintype "passive"))
      (node (ref "DC11") (pin "C") (pinfunction "C_C") (pintype "passive"))
      (node (ref "DC2") (pin "C") (pinfunction "C_C") (pintype "passive"))
      (node (ref "DC3") (pin "C") (pinfunction "C_C") (pintype "passive"))
      (node (ref "DC4") (pin "C") (pinfunction "C_C") (pintype "passive"))
      (node (ref "DC5") (pin "C") (pinfunction "C_C") (pintype "passive"))
      (node (ref "DC6") (pin "C") (pinfunction "C_C") (pintype "passive"))
      (node (ref "DC7") (pin "C") (pinfunction "C_C") (pintype "passive"))
      (node (ref "DC8") (pin "C") (pinfunction "C_C") (pintype "passive"))
      (node (ref "DC9") (pin "C") (pinfunction "C_C") (pintype "passive"))
      (node (ref "U$1") (pin "P$33") (pinfunction "PB12_P$33") (pintype "bidirectional"))
    )
    (net (code "19") (name "KEYROW3") (class "Default")
      (node (ref "DD1") (pin "C") (pinfunction "C_C") (pintype "passive"))
      (node (ref "DD10") (pin "C") (pinfunction "C_C") (pintype "passive"))
      (node (ref "DD11") (pin "C") (pinfunction "C_C") (pintype "passive"))
      (node (ref "DD2") (pin "C") (pinfunction "C_C") (pintype "passive"))
      (node (ref "DD3") (pin "C") (pinfunction "C_C") (pintype "passive"))
      (node (ref "DD4") (pin "C") (pinfunction "C_C") (pintype "passive"))
      (node (ref "DD5") (pin "C") (pinfunction "C_C") (pintype "passive"))
      (node (ref "DD6") (pin "C") (pinfunction "C_C") (pintype "passive"))
      (node (ref "DD7") (pin "C") (pinfunction "C_C") (pintype "passive"))
      (node (ref "DD8") (pin "C") (pinfunction "C_C") (pintype "passive"))
      (node (ref "DD9") (pin "C") (pinfunction "C_C") (pintype "passive"))
      (node (ref "U$1") (pin "P$30") (pinfunction "PB11_P$30") (pintype "bidirectional"))
      (node (ref "U$1") (pin "P$35") (pinfunction "PB14_P$35") (pintype "bidirectional"))
    )
    (net (code "20") (name "NRST") (class "Default")
      (node (ref "R10") (pin "1") (pinfunction "1_1") (pintype "passive"))
      (node (ref "TP6") (pin "TP") (pinfunction "TP_TP") (pintype "input"))
      (node (ref "U$1") (pin "P$7") (pinfunction "NRST_P$7") (pintype "bidirectional"))
    )
    (net (code "21") (name "Net-(BTA1-P$1-PadP$3)") (class "Default")
      (node (ref "BTA1") (pin "P$1") (pinfunction "P$1_P$1") (pintype "bidirectional"))
      (node (ref "BTA1") (pin "P$3") (pinfunction "P$1_P$3") (pintype "bidirectional"))
      (node (ref "DA1") (pin "A") (pinfunction "A_A") (pintype "passive"))
    )
    (net (code "22") (name "Net-(BTA2-P$1-PadP$3)") (class "Default")
      (node (ref "BTA2") (pin "P$1") (pinfunction "P$1_P$1") (pintype "bidirectional"))
      (node (ref "BTA2") (pin "P$3") (pinfunction "P$1_P$3") (pintype "bidirectional"))
      (node (ref "DA2") (pin "A") (pinfunction "A_A") (pintype "passive"))
    )
    (net (code "23") (name "Net-(BTA3-P$1-PadP$3)") (class "Default")
      (node (ref "BTA3") (pin "P$1") (pinfunction "P$1_P$1") (pintype "bidirectional"))
      (node (ref "BTA3") (pin "P$3") (pinfunction "P$1_P$3") (pintype "bidirectional"))
      (node (ref "DA3") (pin "A") (pinfunction "A_A") (pintype "passive"))
    )
    (net (code "24") (name "Net-(BTA4-P$1-PadP$3)") (class "Default")
      (node (ref "BTA4") (pin "P$1") (pinfunction "P$1_P$1") (pintype "bidirectional"))
      (node (ref "BTA4") (pin "P$3") (pinfunction "P$1_P$3") (pintype "bidirectional"))
      (node (ref "DA4") (pin "A") (pinfunction "A_A") (pintype "passive"))
    )
    (net (code "25") (name "Net-(BTA5-P$1-PadP$3)") (class "Default")
      (node (ref "BTA5") (pin "P$1") (pinfunction "P$1_P$1") (pintype "bidirectional"))
      (node (ref "BTA5") (pin "P$3") (pinfunction "P$1_P$3") (pintype "bidirectional"))
      (node (ref "DA5") (pin "A") (pinfunction "A_A") (pintype "passive"))
    )
    (net (code "26") (name "Net-(BTA6-P$1-PadP$3)") (class "Default")
      (node (ref "BTA6") (pin "P$1") (pinfunction "P$1_P$1") (pintype "bidirectional"))
      (node (ref "BTA6") (pin "P$3") (pinfunction "P$1_P$3") (pintype "bidirectional"))
      (node (ref "DA6") (pin "A") (pinfunction "A_A") (pintype "passive"))
    )
    (net (code "27") (name "Net-(BTA7-P$1-PadP$3)") (class "Default")
      (node (ref "BTA7") (pin "P$1") (pinfunction "P$1_P$1") (pintype "bidirectional"))
      (node (ref "BTA7") (pin "P$3") (pinfunction "P$1_P$3") (pintype "bidirectional"))
      (node (ref "DA7") (pin "A") (pinfunction "A_A") (pintype "passive"))
    )
    (net (code "28") (name "Net-(BTA8-P$1-PadP$3)") (class "Default")
      (node (ref "BTA8") (pin "P$1") (pinfunction "P$1_P$1") (pintype "bidirectional"))
      (node (ref "BTA8") (pin "P$3") (pinfunction "P$1_P$3") (pintype "bidirectional"))
      (node (ref "DA8") (pin "A") (pinfunction "A_A") (pintype "passive"))
    )
    (net (code "29") (name "Net-(BTA9-P$1-PadP$3)") (class "Default")
      (node (ref "BTA9") (pin "P$1") (pinfunction "P$1_P$1") (pintype "bidirectional"))
      (node (ref "BTA9") (pin "P$3") (pinfunction "P$1_P$3") (pintype "bidirectional"))
      (node (ref "DA9") (pin "A") (pinfunction "A_A") (pintype "passive"))
    )
    (net (code "30") (name "Net-(BTA10-P$1-PadP$3)") (class "Default")
      (node (ref "BTA10") (pin "P$1") (pinfunction "P$1_P$1") (pintype "bidirectional"))
      (node (ref "BTA10") (pin "P$3") (pinfunction "P$1_P$3") (pintype "bidirectional"))
      (node (ref "DA10") (pin "A") (pinfunction "A_A") (pintype "passive"))
    )
    (net (code "31") (name "Net-(BTA11-P$1-PadP$3)") (class "Default")
      (node (ref "BTA11") (pin "P$1") (pinfunction "P$1_P$1") (pintype "bidirectional"))
      (node (ref "BTA11") (pin "P$3") (pinfunction "P$1_P$3") (pintype "bidirectional"))
      (node (ref "DA11") (pin "A") (pinfunction "A_A") (pintype "passive"))
    )
    (net (code "32") (name "Net-(BTB1-P$1-PadP$3)") (class "Default")
      (node (ref "BTB1") (pin "P$1") (pinfunction "P$1_P$1") (pintype "bidirectional"))
      (node (ref "BTB1") (pin "P$3") (pinfunction "P$1_P$3") (pintype "bidirectional"))
      (node (ref "DB1") (pin "A") (pinfunction "A_A") (pintype "passive"))
    )
    (net (code "33") (name "Net-(BTB2-P$1-PadP$3)") (class "Default")
      (node (ref "BTB2") (pin "P$1") (pinfunction "P$1_P$1") (pintype "bidirectional"))
      (node (ref "BTB2") (pin "P$3") (pinfunction "P$1_P$3") (pintype "bidirectional"))
      (node (ref "DB2") (pin "A") (pinfunction "A_A") (pintype "passive"))
    )
    (net (code "34") (name "Net-(BTB3-P$1-PadP$3)") (class "Default")
      (node (ref "BTB3") (pin "P$1") (pinfunction "P$1_P$1") (pintype "bidirectional"))
      (node (ref "BTB3") (pin "P$3") (pinfunction "P$1_P$3") (pintype "bidirectional"))
      (node (ref "DB3") (pin "A") (pinfunction "A_A") (pintype "passive"))
    )
    (net (code "35") (name "Net-(BTB4-P$1-PadP$3)") (class "Default")
      (node (ref "BTB4") (pin "P$1") (pinfunction "P$1_P$1") (pintype "bidirectional"))
      (node (ref "BTB4") (pin "P$3") (pinfunction "P$1_P$3") (pintype "bidirectional"))
      (node (ref "DB4") (pin "A") (pinfunction "A_A") (pintype "passive"))
    )
    (net (code "36") (name "Net-(BTB5-P$1-PadP$3)") (class "Default")
      (node (ref "BTB5") (pin "P$1") (pinfunction "P$1_P$1") (pintype "bidirectional"))
      (node (ref "BTB5") (pin "P$3") (pinfunction "P$1_P$3") (pintype "bidirectional"))
      (node (ref "DB5") (pin "A") (pinfunction "A_A") (pintype "passive"))
    )
    (net (code "37") (name "Net-(BTB6-P$1-PadP$3)") (class "Default")
      (node (ref "BTB6") (pin "P$1") (pinfunction "P$1_P$1") (pintype "bidirectional"))
      (node (ref "BTB6") (pin "P$3") (pinfunction "P$1_P$3") (pintype "bidirectional"))
      (node (ref "DB6") (pin "A") (pinfunction "A_A") (pintype "passive"))
    )
    (net (code "38") (name "Net-(BTB7-P$1-PadP$3)") (class "Default")
      (node (ref "BTB7") (pin "P$1") (pinfunction "P$1_P$1") (pintype "bidirectional"))
      (node (ref "BTB7") (pin "P$3") (pinfunction "P$1_P$3") (pintype "bidirectional"))
      (node (ref "DB7") (pin "A") (pinfunction "A_A") (pintype "passive"))
    )
    (net (code "39") (name "Net-(BTB8-P$1-PadP$3)") (class "Default")
      (node (ref "BTB8") (pin "P$1") (pinfunction "P$1_P$1") (pintype "bidirectional"))
      (node (ref "BTB8") (pin "P$3") (pinfunction "P$1_P$3") (pintype "bidirectional"))
      (node (ref "DB8") (pin "A") (pinfunction "A_A") (pintype "passive"))
    )
    (net (code "40") (name "Net-(BTB9-P$1-PadP$3)") (class "Default")
      (node (ref "BTB9") (pin "P$1") (pinfunction "P$1_P$1") (pintype "bidirectional"))
      (node (ref "BTB9") (pin "P$3") (pinfunction "P$1_P$3") (pintype "bidirectional"))
      (node (ref "DB9") (pin "A") (pinfunction "A_A") (pintype "passive"))
    )
    (net (code "41") (name "Net-(BTB10-P$1-PadP$3)") (class "Default")
      (node (ref "BTB10") (pin "P$1") (pinfunction "P$1_P$1") (pintype "bidirectional"))
      (node (ref "BTB10") (pin "P$3") (pinfunction "P$1_P$3") (pintype "bidirectional"))
      (node (ref "DB10") (pin "A") (pinfunction "A_A") (pintype "passive"))
    )
    (net (code "42") (name "Net-(BTB11-P$1-PadP$3)") (class "Default")
      (node (ref "BTB11") (pin "P$1") (pinfunction "P$1_P$1") (pintype "bidirectional"))
      (node (ref "BTB11") (pin "P$3") (pinfunction "P$1_P$3") (pintype "bidirectional"))
      (node (ref "DB11") (pin "A") (pinfunction "A_A") (pintype "passive"))
    )
    (net (code "43") (name "Net-(BTC1-P$1-PadP$3)") (class "Default")
      (node (ref "BTC1") (pin "P$1") (pinfunction "P$1_P$1") (pintype "bidirectional"))
      (node (ref "BTC1") (pin "P$3") (pinfunction "P$1_P$3") (pintype "bidirectional"))
      (node (ref "DC1") (pin "A") (pinfunction "A_A") (pintype "passive"))
    )
    (net (code "44") (name "Net-(BTC2-P$1-PadP$3)") (class "Default")
      (node (ref "BTC2") (pin "P$1") (pinfunction "P$1_P$1") (pintype "bidirectional"))
      (node (ref "BTC2") (pin "P$3") (pinfunction "P$1_P$3") (pintype "bidirectional"))
      (node (ref "DC2") (pin "A") (pinfunction "A_A") (pintype "passive"))
    )
    (net (code "45") (name "Net-(BTC3-P$1-PadP$3)") (class "Default")
      (node (ref "BTC3") (pin "P$1") (pinfunction "P$1_P$1") (pintype "bidirectional"))
      (node (ref "BTC3") (pin "P$3") (pinfunction "P$1_P$3") (pintype "bidirectional"))
      (node (ref "DC3") (pin "A") (pinfunction "A_A") (pintype "passive"))
    )
    (net (code "46") (name "Net-(BTC4-P$1-PadP$3)") (class "Default")
      (node (ref "BTC4") (pin "P$1") (pinfunction "P$1_P$1") (pintype "bidirectional"))
      (node (ref "BTC4") (pin "P$3") (pinfunction "P$1_P$3") (pintype "bidirectional"))
      (node (ref "DC4") (pin "A") (pinfunction "A_A") (pintype "passive"))
    )
    (net (code "47") (name "Net-(BTC5-P$1-PadP$3)") (class "Default")
      (node (ref "BTC5") (pin "P$1") (pinfunction "P$1_P$1") (pintype "bidirectional"))
      (node (ref "BTC5") (pin "P$3") (pinfunction "P$1_P$3") (pintype "bidirectional"))
      (node (ref "DC5") (pin "A") (pinfunction "A_A") (pintype "passive"))
    )
    (net (code "48") (name "Net-(BTC6-P$1-PadP$3)") (class "Default")
      (node (ref "BTC6") (pin "P$1") (pinfunction "P$1_P$1") (pintype "bidirectional"))
      (node (ref "BTC6") (pin "P$3") (pinfunction "P$1_P$3") (pintype "bidirectional"))
      (node (ref "DC6") (pin "A") (pinfunction "A_A") (pintype "passive"))
    )
    (net (code "49") (name "Net-(BTC7-P$1-PadP$3)") (class "Default")
      (node (ref "BTC7") (pin "P$1") (pinfunction "P$1_P$1") (pintype "bidirectional"))
      (node (ref "BTC7") (pin "P$3") (pinfunction "P$1_P$3") (pintype "bidirectional"))
      (node (ref "DC7") (pin "A") (pinfunction "A_A") (pintype "passive"))
    )
    (net (code "50") (name "Net-(BTC8-P$1-PadP$3)") (class "Default")
      (node (ref "BTC8") (pin "P$1") (pinfunction "P$1_P$1") (pintype "bidirectional"))
      (node (ref "BTC8") (pin "P$3") (pinfunction "P$1_P$3") (pintype "bidirectional"))
      (node (ref "DC8") (pin "A") (pinfunction "A_A") (pintype "passive"))
    )
    (net (code "51") (name "Net-(BTC9-P$1-PadP$3)") (class "Default")
      (node (ref "BTC9") (pin "P$1") (pinfunction "P$1_P$1") (pintype "bidirectional"))
      (node (ref "BTC9") (pin "P$3") (pinfunction "P$1_P$3") (pintype "bidirectional"))
      (node (ref "DC9") (pin "A") (pinfunction "A_A") (pintype "passive"))
    )
    (net (code "52") (name "Net-(BTC10-P$1-PadP$3)") (class "Default")
      (node (ref "BTC10") (pin "P$1") (pinfunction "P$1_P$1") (pintype "bidirectional"))
      (node (ref "BTC10") (pin "P$3") (pinfunction "P$1_P$3") (pintype "bidirectional"))
      (node (ref "DC10") (pin "A") (pinfunction "A_A") (pintype "passive"))
    )
    (net (code "53") (name "Net-(BTC11-P$1-PadP$3)") (class "Default")
      (node (ref "BTC11") (pin "P$1") (pinfunction "P$1_P$1") (pintype "bidirectional"))
      (node (ref "BTC11") (pin "P$3") (pinfunction "P$1_P$3") (pintype "bidirectional"))
      (node (ref "DC11") (pin "A") (pinfunction "A_A") (pintype "passive"))
    )
    (net (code "54") (name "Net-(BTD1-P$1-PadP$3)") (class "Default")
      (node (ref "BTD1") (pin "P$1") (pinfunction "P$1_P$1") (pintype "bidirectional"))
      (node (ref "BTD1") (pin "P$3") (pinfunction "P$1_P$3") (pintype "bidirectional"))
      (node (ref "DD1") (pin "A") (pinfunction "A_A") (pintype "passive"))
    )
    (net (code "55") (name "Net-(BTD2-P$1-PadP$3)") (class "Default")
      (node (ref "BTD2") (pin "P$1") (pinfunction "P$1_P$1") (pintype "bidirectional"))
      (node (ref "BTD2") (pin "P$3") (pinfunction "P$1_P$3") (pintype "bidirectional"))
      (node (ref "DD2") (pin "A") (pinfunction "A_A") (pintype "passive"))
    )
    (net (code "56") (name "Net-(BTD3-P$1-PadP$3)") (class "Default")
      (node (ref "BTD3") (pin "P$1") (pinfunction "P$1_P$1") (pintype "bidirectional"))
      (node (ref "BTD3") (pin "P$3") (pinfunction "P$1_P$3") (pintype "bidirectional"))
      (node (ref "DD3") (pin "A") (pinfunction "A_A") (pintype "passive"))
    )
    (net (code "57") (name "Net-(BTD4-P$1-PadP$3)") (class "Default")
      (node (ref "BTD4") (pin "P$1") (pinfunction "P$1_P$1") (pintype "bidirectional"))
      (node (ref "BTD4") (pin "P$3") (pinfunction "P$1_P$3") (pintype "bidirectional"))
      (node (ref "DD4") (pin "A") (pinfunction "A_A") (pintype "passive"))
    )
    (net (code "58") (name "Net-(BTD5-P$1-PadP$3)") (class "Default")
      (node (ref "BTD5") (pin "P$1") (pinfunction "P$1_P$1") (pintype "bidirectional"))
      (node (ref "BTD5") (pin "P$3") (pinfunction "P$1_P$3") (pintype "bidirectional"))
      (node (ref "DD5") (pin "A") (pinfunction "A_A") (pintype "passive"))
    )
    (net (code "59") (name "Net-(BTD6-P$1-PadP$3)") (class "Default")
      (node (ref "BTD6") (pin "P$1") (pinfunction "P$1_P$1") (pintype "bidirectional"))
      (node (ref "BTD6") (pin "P$3") (pinfunction "P$1_P$3") (pintype "bidirectional"))
      (node (ref "DD6") (pin "A") (pinfunction "A_A") (pintype "passive"))
    )
    (net (code "60") (name "Net-(BTD7-P$1-PadP$3)") (class "Default")
      (node (ref "BTD7") (pin "P$1") (pinfunction "P$1_P$1") (pintype "bidirectional"))
      (node (ref "BTD7") (pin "P$3") (pinfunction "P$1_P$3") (pintype "bidirectional"))
      (node (ref "DD7") (pin "A") (pinfunction "A_A") (pintype "passive"))
    )
    (net (code "61") (name "Net-(BTD8-P$1-PadP$3)") (class "Default")
      (node (ref "BTD8") (pin "P$1") (pinfunction "P$1_P$1") (pintype "bidirectional"))
      (node (ref "BTD8") (pin "P$3") (pinfunction "P$1_P$3") (pintype "bidirectional"))
      (node (ref "DD8") (pin "A") (pinfunction "A_A") (pintype "passive"))
    )
    (net (code "62") (name "Net-(BTD9-P$1-PadP$3)") (class "Default")
      (node (ref "BTD9") (pin "P$1") (pinfunction "P$1_P$1") (pintype "bidirectional"))
      (node (ref "BTD9") (pin "P$3") (pinfunction "P$1_P$3") (pintype "bidirectional"))
      (node (ref "DD9") (pin "A") (pinfunction "A_A") (pintype "passive"))
    )
    (net (code "63") (name "Net-(BTD10-P$1-PadP$3)") (class "Default")
      (node (ref "BTD10") (pin "P$1") (pinfunction "P$1_P$1") (pintype "bidirectional"))
      (node (ref "BTD10") (pin "P$3") (pinfunction "P$1_P$3") (pintype "bidirectional"))
      (node (ref "DD10") (pin "A") (pinfunction "A_A") (pintype "passive"))
    )
    (net (code "64") (name "Net-(BTD11-P$1-PadP$3)") (class "Default")
      (node (ref "BTD11") (pin "P$1") (pinfunction "P$1_P$1") (pintype "bidirectional"))
      (node (ref "BTD11") (pin "P$3") (pinfunction "P$1_P$3") (pintype "bidirectional"))
      (node (ref "DD11") (pin "A") (pinfunction "A_A") (pintype "passive"))
    )
    (net (code "65") (name "Net-(DA1-PadC)") (class "Default")
      (node (ref "DA1") (pin "C") (pinfunction "C_C") (pintype "passive"))
      (node (ref "DA10") (pin "C") (pinfunction "C_C") (pintype "passive"))
      (node (ref "DA11") (pin "C") (pinfunction "C_C") (pintype "passive"))
      (node (ref "DA2") (pin "C") (pinfunction "C_C") (pintype "passive"))
      (node (ref "DA3") (pin "C") (pinfunction "C_C") (pintype "passive"))
      (node (ref "DA4") (pin "C") (pinfunction "C_C") (pintype "passive"))
      (node (ref "DA5") (pin "C") (pinfunction "C_C") (pintype "passive"))
      (node (ref "DA6") (pin "C") (pinfunction "C_C") (pintype "passive"))
      (node (ref "DA7") (pin "C") (pinfunction "C_C") (pintype "passive"))
      (node (ref "DA8") (pin "C") (pinfunction "C_C") (pintype "passive"))
      (node (ref "DA9") (pin "C") (pinfunction "C_C") (pintype "passive"))
    )
    (net (code "66") (name "Net-(LED1-PadA)") (class "Default")
      (node (ref "LED1") (pin "A") (pinfunction "A_A") (pintype "passive"))
      (node (ref "R11") (pin "2") (pinfunction "2_2") (pintype "passive"))
    )
    (net (code "67") (name "Net-(LED2-PadA)") (class "Default")
      (node (ref "LED2") (pin "A") (pinfunction "A_A") (pintype "passive"))
      (node (ref "R12") (pin "2") (pinfunction "2_2") (pintype "passive"))
    )
    (net (code "68") (name "Net-(U$1B-PA11)") (class "Default")
      (node (ref "LED1") (pin "C") (pinfunction "C_C") (pintype "passive"))
      (node (ref "U$1") (pin "P$44") (pinfunction "PA11_P$44") (pintype "bidirectional"))
    )
    (net (code "69") (name "Net-(U$1E-PH0)") (class "Default")
      (node (ref "C13") (pin "1") (pinfunction "1_1") (pintype "passive"))
      (node (ref "U$1") (pin "P$5") (pinfunction "PH0_P$5") (pintype "bidirectional"))
      (node (ref "U$7") (pin "P$1") (pinfunction "P1_P$1") (pintype "bidirectional"))
    )
    (net (code "70") (name "Net-(U$1E-PH1)") (class "Default")
      (node (ref "C14") (pin "1") (pinfunction "1_1") (pintype "passive"))
      (node (ref "U$1") (pin "P$6") (pinfunction "PH1_P$6") (pintype "bidirectional"))
      (node (ref "U$7") (pin "P$3") (pinfunction "P2_P$3") (pintype "bidirectional"))
    )
    (net (code "71") (name "Net-(U$3-VBUS)") (class "Default")
      (node (ref "C15") (pin "1") (pinfunction "1_1") (pintype "passive"))
      (node (ref "U$3") (pin "P$1") (pinfunction "VBUS_P$1") (pintype "bidirectional"))
      (node (ref "U$8") (pin "P$6") (pinfunction "VIN_P$6") (pintype "bidirectional"))
    )
    (net (code "72") (name "Net-(U$4-FB)") (class "Default")
      (node (ref "R1") (pin "1") (pinfunction "1_1") (pintype "passive"))
      (node (ref "R2") (pin "2") (pinfunction "2_2") (pintype "passive"))
      (node (ref "U$4") (pin "P5") (pinfunction "FB_P5") (pintype "bidirectional"))
    )
    (net (code "73") (name "Net-(U$4-LX-PadP11)") (class "Default")
      (node (ref "U$4") (pin "P11") (pinfunction "LX_P11") (pintype "bidirectional"))
      (node (ref "U$4") (pin "P12") (pinfunction "LX_P12") (pintype "bidirectional"))
      (node (ref "U$5") (pin "P$2") (pinfunction "P$2_P$2") (pintype "bidirectional"))
    )
    (net (code "74") (name "Net-(U$4-VMID)") (class "Default")
      (node (ref "C3") (pin "1") (pinfunction "1_1") (pintype "passive"))
      (node (ref "U$4") (pin "P1") (pinfunction "VMID_P1") (pintype "bidirectional"))
    )
    (net (code "75") (name "Net-(U$4-VO_SET)") (class "Default")
      (node (ref "R1") (pin "2") (pinfunction "2_2") (pintype "passive"))
      (node (ref "U$4") (pin "P3") (pinfunction "VO_SET_P3") (pintype "bidirectional"))
    )
    (net (code "76") (name "Net-(U$6-SW)") (class "Default")
      (node (ref "L1") (pin "1") (pinfunction "1_1") (pintype "passive"))
      (node (ref "U$6") (pin "A1") (pinfunction "SW_A1") (pintype "bidirectional"))
    )
    (net (code "77") (name "Net-(U$8-ISET)") (class "Default")
      (node (ref "R4") (pin "1") (pinfunction "1_1") (pintype "passive"))
      (node (ref "U$8") (pin "P$4") (pinfunction "ISET_P$4") (pintype "bidirectional"))
    )
    (net (code "78") (name "Net-(U$8-TS)") (class "Default")
      (node (ref "R5") (pin "1") (pinfunction "1_1") (pintype "passive"))
      (node (ref "U$8") (pin "P$1") (pinfunction "TS_P$1") (pintype "bidirectional"))
    )
    (net (code "79") (name "Net-(X1N-1)") (class "Default")
      (node (ref "R3") (pin "1") (pinfunction "1_1") (pintype "passive"))
      (node (ref "X1") (pin "21") (pinfunction "1_21") (pintype "passive"))
    )
    (net (code "80") (name "Net-(X1O-1)") (class "Default")
      (node (ref "C10") (pin "2") (pinfunction "2_2") (pintype "passive"))
      (node (ref "X1") (pin "22") (pinfunction "1_22") (pintype "passive"))
    )
    (net (code "81") (name "PA3") (class "Default")
      (node (ref "U$1") (pin "P$17") (pinfunction "PA3_P$17") (pintype "bidirectional"))
      (node (ref "X1") (pin "10") (pinfunction "1_10") (pintype "passive"))
    )
    (net (code "82") (name "PA13") (class "Default")
      (node (ref "TP2") (pin "TP") (pinfunction "TP_TP") (pintype "input"))
      (node (ref "U$1") (pin "P$46") (pinfunction "PA13_P$46") (pintype "bidirectional"))
    )
    (net (code "83") (name "PA14") (class "Default")
      (node (ref "TP3") (pin "TP") (pinfunction "TP_TP") (pintype "input"))
      (node (ref "U$1") (pin "P$49") (pinfunction "PA14_P$49") (pintype "bidirectional"))
    )
    (net (code "84") (name "SD_CLK") (class "Default")
      (node (ref "U$1") (pin "P$53") (pinfunction "PC12_P$53") (pintype "bidirectional"))
      (node (ref "U$2") (pin "P$5") (pinfunction "CLK_P$5") (pintype "bidirectional"))
    )
    (net (code "85") (name "SD_CMD") (class "Default")
      (node (ref "U$1") (pin "P$54") (pinfunction "PD2_P$54") (pintype "bidirectional"))
      (node (ref "U$2") (pin "P$3") (pinfunction "CMD_P$3") (pintype "bidirectional"))
    )
    (net (code "86") (name "SD_DAT0") (class "Default")
      (node (ref "U$1") (pin "P$39") (pinfunction "PC8_P$39") (pintype "bidirectional"))
      (node (ref "U$2") (pin "P$7") (pinfunction "DAT0_P$7") (pintype "bidirectional"))
    )
    (net (code "87") (name "SD_DAT1") (class "Default")
      (node (ref "U$1") (pin "P$40") (pinfunction "PC9_P$40") (pintype "bidirectional"))
      (node (ref "U$2") (pin "P$8") (pinfunction "DAT1_P$8") (pintype "bidirectional"))
    )
    (net (code "88") (name "SD_DAT2") (class "Default")
      (node (ref "U$1") (pin "P$51") (pinfunction "PC10_P$51") (pintype "bidirectional"))
      (node (ref "U$2") (pin "P$1") (pinfunction "DAT2_P$1") (pintype "bidirectional"))
    )
    (net (code "89") (name "SD_DAT3") (class "Default")
      (node (ref "U$1") (pin "P$52") (pinfunction "PC11_P$52") (pintype "bidirectional"))
      (node (ref "U$2") (pin "P$2") (pinfunction "CD/DAT3_P$2") (pintype "bidirectional"))
    )
    (net (code "90") (name "SD_SWITCH") (class "Default")
      (node (ref "R8") (pin "2") (pinfunction "2_2") (pintype "passive"))
      (node (ref "U$1") (pin "P$50") (pinfunction "PA15_P$50") (pintype "bidirectional"))
      (node (ref "U$2") (pin "P$10") (pinfunction "P$10_P$10") (pintype "bidirectional"))
    )
    (net (code "91") (name "SPI_CS") (class "Default")
      (node (ref "U$1") (pin "P$20") (pinfunction "PA4_P$20") (pintype "bidirectional"))
      (node (ref "X1") (pin "8") (pinfunction "1_8") (pintype "passive"))
    )
    (net (code "92") (name "SPI_MOSI") (class "Default")
      (node (ref "U$1") (pin "P$23") (pinfunction "PA7_P$23") (pintype "bidirectional"))
      (node (ref "X1") (pin "14") (pinfunction "1_14") (pintype "passive"))
    )
    (net (code "93") (name "SPI_SCK") (class "Default")
      (node (ref "U$1") (pin "P$21") (pinfunction "PA5_P$21") (pintype "bidirectional"))
      (node (ref "X1") (pin "13") (pinfunction "1_13") (pintype "passive"))
    )
    (net (code "94") (name "V+") (class "Default")
      (node (ref "C16") (pin "1") (pinfunction "1_1") (pintype "passive"))
      (node (ref "TP7") (pin "TP") (pinfunction "TP_TP") (pintype "input"))
      (node (ref "U$8") (pin "P$2") (pinfunction "VOUT_P$2") (pintype "bidirectional"))
      (node (ref "U$9") (pin "P$1") (pinfunction "COM_P$1") (pintype "bidirectional"))
    )
    (net (code "95") (name "VCC") (class "Default")
      (node (ref "C1") (pin "1") (pinfunction "1_1") (pintype "passive"))
      (node (ref "C11") (pin "1") (pinfunction "1_1") (pintype "passive"))
      (node (ref "C17") (pin "1") (pinfunction "1_1") (pintype "passive"))
      (node (ref "R6") (pin "2") (pinfunction "2_2") (pintype "passive"))
      (node (ref "U$4") (pin "P8") (pinfunction "VIN_P8") (pintype "bidirectional"))
      (node (ref "U$5") (pin "P$1") (pinfunction "P$1_P$1") (pintype "bidirectional"))
      (node (ref "U$6") (pin "A2") (pinfunction "VIN_A2") (pintype "bidirectional"))
      (node (ref "U$6") (pin "B1") (pinfunction "EN_B1") (pintype "bidirectional"))
      (node (ref "U$6") (pin "C1") (pinfunction "VSEL1_C1") (pintype "bidirectional"))
      (node (ref "U$6") (pin "D1") (pinfunction "VSEL2_D1") (pintype "bidirectional"))
      (node (ref "U$6") (pin "D2") (pinfunction "VSEL3_D2") (pintype "bidirectional"))
      (node (ref "U$9") (pin "P$3") (pinfunction "L_P$3") (pintype "bidirectional"))
    )
    (net (code "96") (name "VCC{slash}2") (class "Default")
      (node (ref "C19") (pin "2") (pinfunction "2_2") (pintype "passive"))
      (node (ref "C2") (pin "1") (pinfunction "1_1") (pintype "passive"))
      (node (ref "U$4") (pin "P2") (pinfunction "VOUT_P2") (pintype "bidirectional"))
      (node (ref "X1") (pin "23") (pinfunction "1_23") (pintype "passive"))
    )
    (net (code "97") (name "unconnected-(U$1B-PA0-PadP$14)") (class "Default")
      (node (ref "U$1") (pin "P$14") (pinfunction "PA0_P$14") (pintype "bidirectional"))
    )
    (net (code "98") (name "unconnected-(U$1B-PA1-PadP$15)") (class "Default")
      (node (ref "U$1") (pin "P$15") (pinfunction "PA1_P$15") (pintype "bidirectional"))
    )
    (net (code "99") (name "unconnected-(U$1B-PA2-PadP$16)") (class "Default")
      (node (ref "U$1") (pin "P$16") (pinfunction "PA2_P$16") (pintype "bidirectional"))
    )
    (net (code "100") (name "unconnected-(U$1B-PA6-PadP$22)") (class "Default")
      (node (ref "U$1") (pin "P$22") (pinfunction "PA6_P$22") (pintype "bidirectional"))
    )
    (net (code "101") (name "unconnected-(U$1B-PA8-PadP$41)") (class "Default")
      (node (ref "U$1") (pin "P$41") (pinfunction "PA8_P$41") (pintype "bidirectional"))
    )
    (net (code "102") (name "unconnected-(U$1B-PA9-PadP$42)") (class "Default")
      (node (ref "U$1") (pin "P$42") (pinfunction "PA9_P$42") (pintype "bidirectional"))
    )
    (net (code "103") (name "unconnected-(U$1B-PA10-PadP$43)") (class "Default")
      (node (ref "U$1") (pin "P$43") (pinfunction "PA10_P$43") (pintype "bidirectional"))
    )
    (net (code "104") (name "unconnected-(U$1B-PA12-PadP$45)") (class "Default")
      (node (ref "U$1") (pin "P$45") (pinfunction "PA12_P$45") (pintype "bidirectional"))
    )
    (net (code "105") (name "unconnected-(U$1C-PB15-PadP$36)") (class "Default")
      (node (ref "U$1") (pin "P$36") (pinfunction "PB15_P$36") (pintype "bidirectional"))
    )
    (net (code "106") (name "unconnected-(U$1D-PC0-PadP$8)") (class "Default")
      (node (ref "U$1") (pin "P$8") (pinfunction "PC0_P$8") (pintype "bidirectional"))
    )
    (net (code "107") (name "unconnected-(U$1D-PC1-PadP$9)") (class "Default")
      (node (ref "U$1") (pin "P$9") (pinfunction "PC1_P$9") (pintype "bidirectional"))
    )
    (net (code "108") (name "unconnected-(U$1D-PC2-PadP$10)") (class "Default")
      (node (ref "U$1") (pin "P$10") (pinfunction "PC2_P$10") (pintype "bidirectional"))
    )
    (net (code "109") (name "unconnected-(U$1D-PC3-PadP$11)") (class "Default")
      (node (ref "U$1") (pin "P$11") (pinfunction "PC3_P$11") (pintype "bidirectional"))
    )
    (net (code "110") (name "unconnected-(U$1D-PC4-PadP$24)") (class "Default")
      (node (ref "U$1") (pin "P$24") (pinfunction "PC4_P$24") (pintype "bidirectional"))
    )
    (net (code "111") (name "unconnected-(U$1D-PC6-PadP$37)") (class "Default")
      (node (ref "U$1") (pin "P$37") (pinfunction "PC6_P$37") (pintype "bidirectional"))
    )
    (net (code "112") (name "unconnected-(U$1D-PC7-PadP$38)") (class "Default")
      (node (ref "U$1") (pin "P$38") (pinfunction "PC7_P$38") (pintype "bidirectional"))
    )
    (net (code "113") (name "unconnected-(U$1D-PC13-PadP$2)") (class "Default")
      (node (ref "U$1") (pin "P$2") (pinfunction "PC13_P$2") (pintype "bidirectional"))
    )
    (net (code "114") (name "unconnected-(U$1D-PC14-PadP$3)") (class "Default")
      (node (ref "U$1") (pin "P$3") (pinfunction "PC14_P$3") (pintype "bidirectional"))
    )
    (net (code "115") (name "unconnected-(U$1D-PC15-PadP$4)") (class "Default")
      (node (ref "U$1") (pin "P$4") (pinfunction "PC15_P$4") (pintype "bidirectional"))
    )
    (net (code "116") (name "unconnected-(U$3-D+-PadP$3)") (class "Default")
      (node (ref "U$3") (pin "P$3") (pinfunction "D+_P$3") (pintype "bidirectional"))
    )
    (net (code "117") (name "unconnected-(U$3-D--PadP$2)") (class "Default")
      (node (ref "U$3") (pin "P$2") (pinfunction "D-_P$2") (pintype "bidirectional"))
    )
    (net (code "118") (name "unconnected-(U$3-ID-PadP$4)") (class "Default")
      (node (ref "U$3") (pin "P$4") (pinfunction "ID_P$4") (pintype "bidirectional"))
    )
    (net (code "119") (name "unconnected-(U$8-CHG-PadP$3)") (class "Default")
      (node (ref "U$8") (pin "P$3") (pinfunction "CHG_P$3") (pintype "bidirectional"))
    )
    (net (code "120") (name "unconnected-(U$9-R-PadP$2)") (class "Default")
      (node (ref "U$9") (pin "P$2") (pinfunction "R_P$2") (pintype "bidirectional"))
    )
    (net (code "121") (name "unconnected-(X1-Pad1)") (class "Default")
      (node (ref "X1") (pin "1") (pinfunction "1_1") (pintype "passive"))
    )
    (net (code "122") (name "unconnected-(X1G-1-Pad15)") (class "Default")
      (node (ref "X1") (pin "15") (pinfunction "1_15") (pintype "passive"))
    )
    (net (code "123") (name "unconnected-(X1Q-1-Pad24)") (class "Default")
      (node (ref "X1") (pin "24") (pinfunction "1_24") (pintype "passive"))
    )
    (net (code "124") (name "unconnected-(X1S-1-Pad4)") (class "Default")
      (node (ref "X1") (pin "4") (pinfunction "1_4") (pintype "passive"))
    )
  )
)
